# breakout.net
KiCad netlist of a schematic drawn in EAGLE
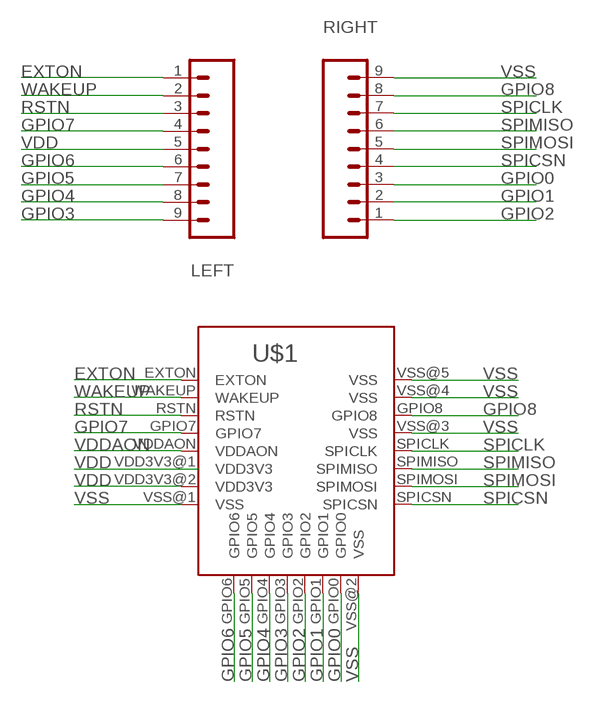
[diagram p0: schematic, sheet 1]

(export (version "E")
  (design (tool "Eeschema 10.0.6"))
  (components
    (comp (ref "LEFT")
      (value "M09")
      (footprint "eagle-import:1X09")
      (libsource (lib "eagle-import") (part "M09"))
    )
    (comp (ref "RIGHT")
      (value "M09")
      (footprint "eagle-import:1X09")
      (libsource (lib "eagle-import") (part "M09"))
    )
    (comp (ref "U$1")
      (value "DWM1000")
      (footprint "eagle-import:DWM1000")
      (libsource (lib "eagle-import") (part "DWM1000"))
    )
  )
  (nets
    (net (code "1") (name "/EXTON") (class "Default")
      (node (ref "LEFT") (pin "1") (pinfunction "1_1") (pintype "passive"))
      (node (ref "U$1") (pin "EXTON") (pinfunction "EXTON_EXTON") (pintype "bidirectional"))
    )
    (net (code "2") (name "/GPIO0") (class "Default")
      (node (ref "RIGHT") (pin "3") (pinfunction "3_3") (pintype "passive"))
      (node (ref "U$1") (pin "GPIO0") (pinfunction "GPIO0_GPIO0") (pintype "bidirectional"))
    )
    (net (code "3") (name "/GPIO1") (class "Default")
      (node (ref "RIGHT") (pin "2") (pinfunction "2_2") (pintype "passive"))
      (node (ref "U$1") (pin "GPIO1") (pinfunction "GPIO1_GPIO1") (pintype "bidirectional"))
    )
    (net (code "4") (name "/GPIO2") (class "Default")
      (node (ref "RIGHT") (pin "1") (pinfunction "1_1") (pintype "passive"))
      (node (ref "U$1") (pin "GPIO2") (pinfunction "GPIO2_GPIO2") (pintype "bidirectional"))
    )
    (net (code "5") (name "/GPIO3") (class "Default")
      (node (ref "LEFT") (pin "9") (pinfunction "9_9") (pintype "passive"))
      (node (ref "U$1") (pin "GPIO3") (pinfunction "GPIO3_GPIO3") (pintype "bidirectional"))
    )
    (net (code "6") (name "/GPIO4") (class "Default")
      (node (ref "LEFT") (pin "8") (pinfunction "8_8") (pintype "passive"))
      (node (ref "U$1") (pin "GPIO4") (pinfunction "GPIO4_GPIO4") (pintype "bidirectional"))
    )
    (net (code "7") (name "/GPIO5") (class "Default")
      (node (ref "LEFT") (pin "7") (pinfunction "7_7") (pintype "passive"))
      (node (ref "U$1") (pin "GPIO5") (pinfunction "GPIO5_GPIO5") (pintype "bidirectional"))
    )
    (net (code "8") (name "/GPIO6") (class "Default")
      (node (ref "LEFT") (pin "6") (pinfunction "6_6") (pintype "passive"))
      (node (ref "U$1") (pin "GPIO6") (pinfunction "GPIO6_GPIO6") (pintype "bidirectional"))
    )
    (net (code "9") (name "/GPIO7") (class "Default")
      (node (ref "LEFT") (pin "4") (pinfunction "4_4") (pintype "passive"))
      (node (ref "U$1") (pin "GPIO7") (pinfunction "GPIO7_GPIO7") (pintype "bidirectional"))
    )
    (net (code "10") (name "/GPIO8") (class "Default")
      (node (ref "RIGHT") (pin "8") (pinfunction "8_8") (pintype "passive"))
      (node (ref "U$1") (pin "GPIO8") (pinfunction "GPIO8_GPIO8") (pintype "bidirectional"))
    )
    (net (code "11") (name "/RSTN") (class "Default")
      (node (ref "LEFT") (pin "3") (pinfunction "3_3") (pintype "passive"))
      (node (ref "U$1") (pin "RSTN") (pinfunction "RSTN_RSTN") (pintype "bidirectional"))
    )
    (net (code "12") (name "/SPICLK") (class "Default")
      (node (ref "RIGHT") (pin "7") (pinfunction "7_7") (pintype "passive"))
      (node (ref "U$1") (pin "SPICLK") (pinfunction "SPICLK_SPICLK") (pintype "bidirectional"))
    )
    (net (code "13") (name "/SPICSN") (class "Default")
      (node (ref "RIGHT") (pin "4") (pinfunction "4_4") (pintype "passive"))
      (node (ref "U$1") (pin "SPICSN") (pinfunction "SPICSN_SPICSN") (pintype "bidirectional"))
    )
    (net (code "14") (name "/SPIMISO") (class "Default")
      (node (ref "RIGHT") (pin "6") (pinfunction "6_6") (pintype "passive"))
      (node (ref "U$1") (pin "SPIMISO") (pinfunction "SPIMISO_SPIMISO") (pintype "bidirectional"))
    )
    (net (code "15") (name "/SPIMOSI") (class "Default")
      (node (ref "RIGHT") (pin "5") (pinfunction "5_5") (pintype "passive"))
      (node (ref "U$1") (pin "SPIMOSI") (pinfunction "SPIMOSI_SPIMOSI") (pintype "bidirectional"))
    )
    (net (code "16") (name "/VDD") (class "Default")
      (node (ref "LEFT") (pin "5") (pinfunction "5_5") (pintype "passive"))
      (node (ref "U$1") (pin "VDD3V3@2") (pinfunction "VDD3V3_VDD3V3@2") (pintype "power_in"))
    )
    (net (code "17") (name "/VDD3V3") (class "Default")
      (node (ref "U$1") (pin "VDD3V3@1") (pinfunction "VDD3V3_VDD3V3@1") (pintype "power_in"))
    )
    (net (code "18") (name "/VDDAON") (class "Default")
      (node (ref "U$1") (pin "VDDAON") (pinfunction "VDDAON_VDDAON") (pintype "power_in"))
    )
    (net (code "19") (name "/VSS") (class "Default")
      (node (ref "RIGHT") (pin "9") (pinfunction "9_9") (pintype "passive"))
      (node (ref "U$1") (pin "VSS@1") (pinfunction "VSS_VSS@1") (pintype "power_in"))
      (node (ref "U$1") (pin "VSS@2") (pinfunction "VSS_VSS@2") (pintype "power_in"))
      (node (ref "U$1") (pin "VSS@3") (pinfunction "VSS_VSS@3") (pintype "power_in"))
      (node (ref "U$1") (pin "VSS@4") (pinfunction "VSS_VSS@4") (pintype "power_in"))
      (node (ref "U$1") (pin "VSS@5") (pinfunction "VSS_VSS@5") (pintype "power_in"))
    )
    (net (code "20") (name "/WAKEUP") (class "Default")
      (node (ref "LEFT") (pin "2") (pinfunction "2_2") (pintype "passive"))
      (node (ref "U$1") (pin "WAKEUP") (pinfunction "WAKEUP_WAKEUP") (pintype "bidirectional"))
    )
  )
)
